# schematic.net
KiCad netlist of a schematic drawn in EAGLE
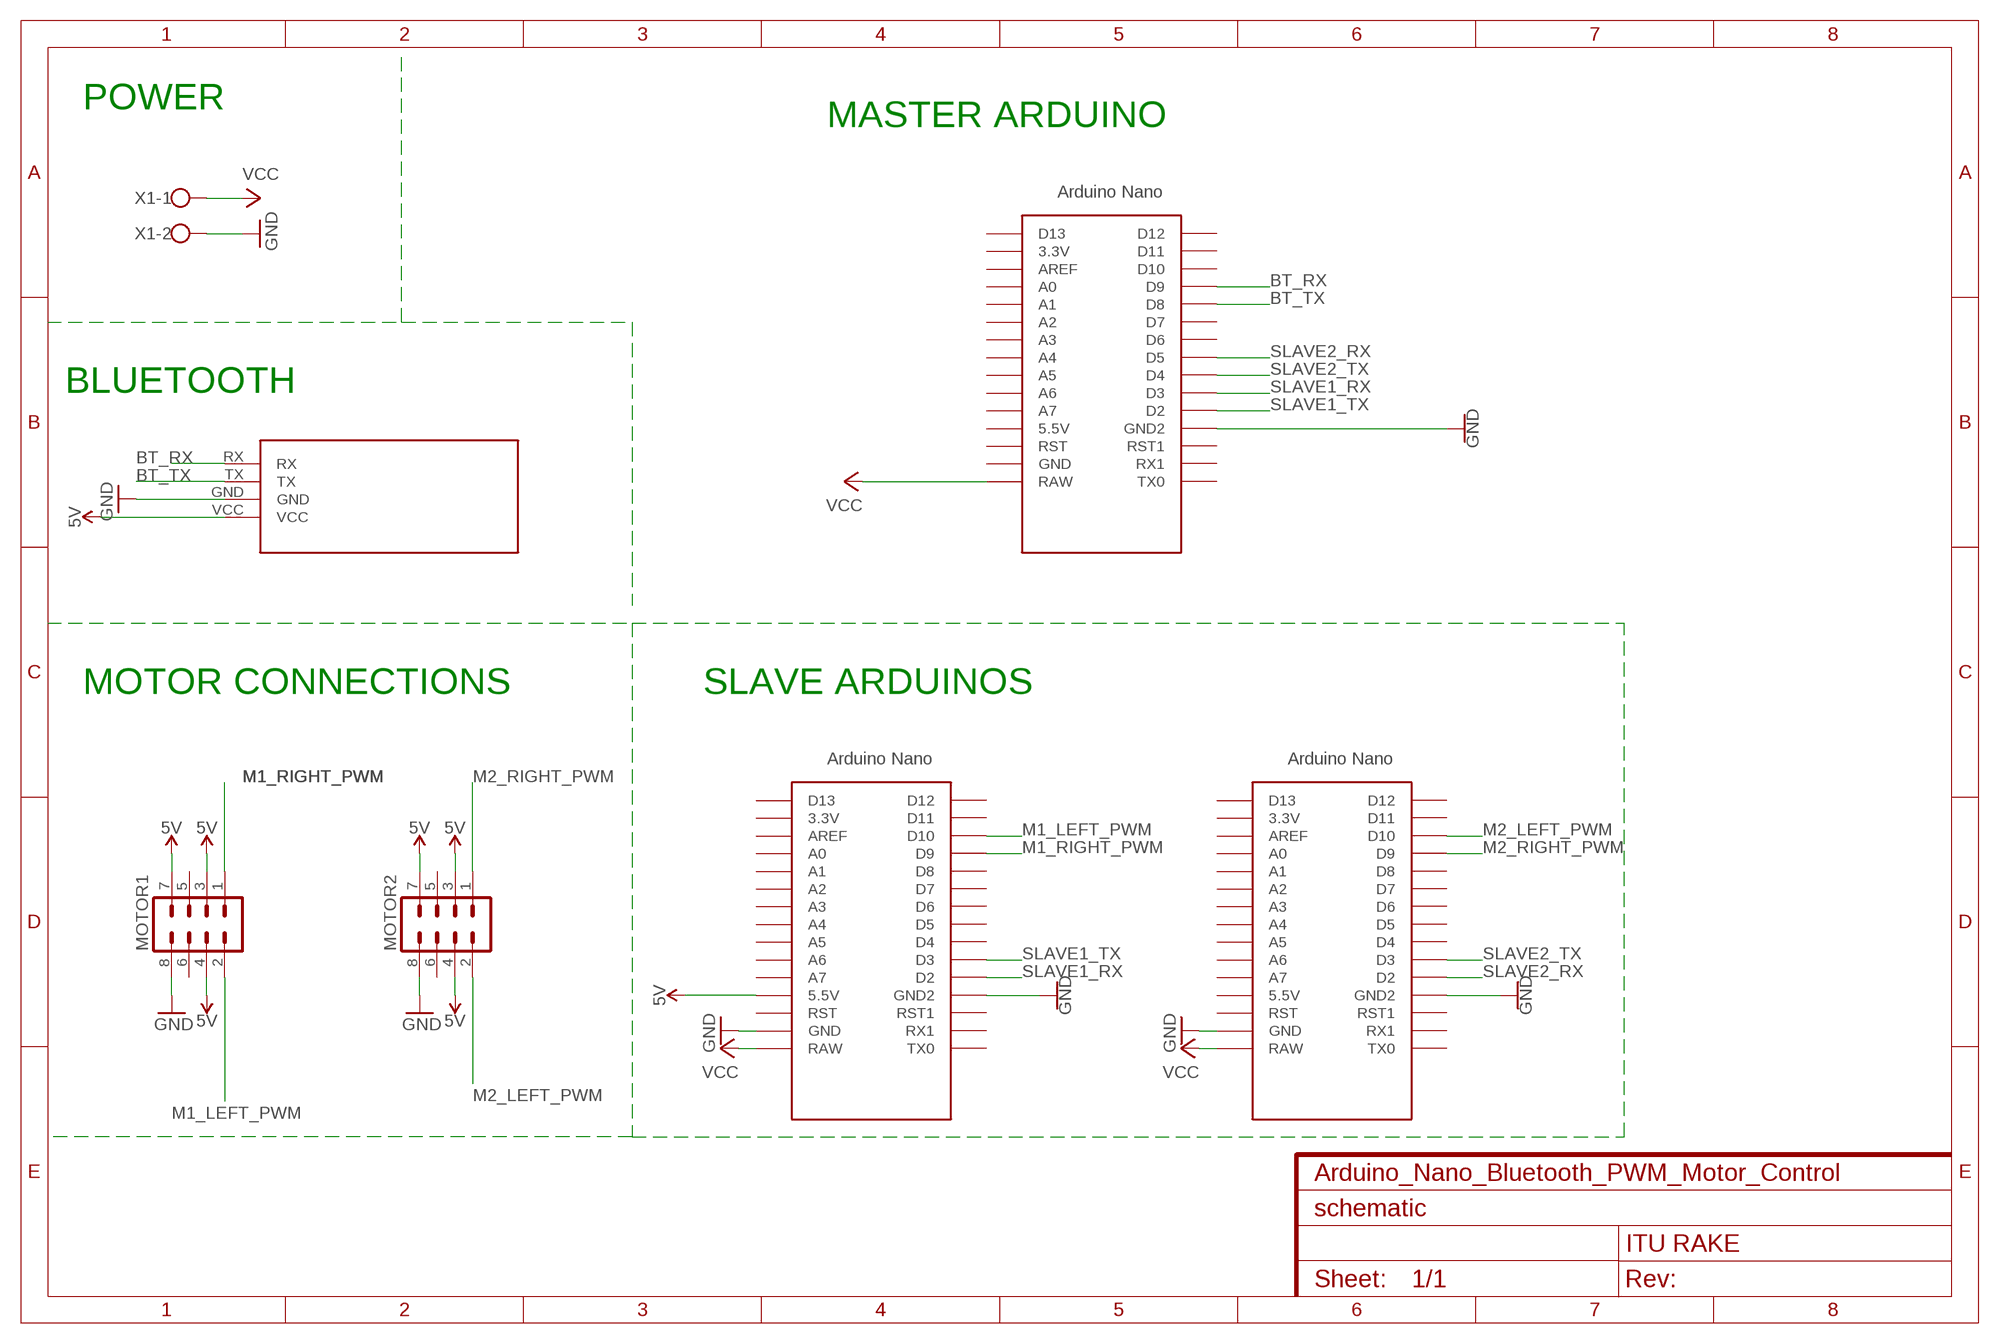
[diagram p0: schematic, sheet 1]

(export (version "E")
  (design (tool "Eeschema 10.0.6"))
  (components
    (comp (ref "BT")
      (value "HC06_BLUETOOTH")
      (footprint "eagle-import:HC06_BT_FOOTPRıNT")
      (libsource (lib "eagle-import") (part "HC06_BLUETOOTH"))
    )
    (comp (ref "MOTOR1")
      (value "MA04-2")
      (footprint "eagle-import:MA04-2")
      (libsource (lib "eagle-import") (part "MA04-2"))
    )
    (comp (ref "MOTOR2")
      (value "MA04-2")
      (footprint "eagle-import:MA04-2")
      (libsource (lib "eagle-import") (part "MA04-2"))
    )
    (comp (ref "U$1")
      (value "NANO")
      (footprint "eagle-import:NANO")
      (libsource (lib "eagle-import") (part "NANO"))
    )
    (comp (ref "U$2")
      (value "NANO")
      (footprint "eagle-import:NANO")
      (libsource (lib "eagle-import") (part "NANO"))
    )
    (comp (ref "U$3")
      (value "NANO")
      (footprint "eagle-import:NANO")
      (libsource (lib "eagle-import") (part "NANO"))
    )
    (comp (ref "X1")
      (value "W237-102")
      (footprint "eagle-import:W237-102")
      (fields (field (name "MPN") "237-102"))
      (libsource (lib "eagle-import") (part "W237-102"))
    )
  )
  (nets
    (net (code "1") (name "/BT_RX") (class "Default")
      (node (ref "BT") (pin "RX") (pinfunction "RX_RX") (pintype "bidirectional"))
      (node (ref "U$1") (pin "D9") (pinfunction "D9_D9") (pintype "bidirectional"))
    )
    (net (code "2") (name "/BT_TX") (class "Default")
      (node (ref "BT") (pin "TX") (pinfunction "TX_TX") (pintype "bidirectional"))
      (node (ref "U$1") (pin "D8") (pinfunction "D8_D8") (pintype "bidirectional"))
    )
    (net (code "3") (name "/M1_LEFT_PWM") (class "Default")
      (node (ref "MOTOR1") (pin "2") (pinfunction "2_2") (pintype "passive"))
      (node (ref "U$2") (pin "D10") (pinfunction "D10_D10") (pintype "bidirectional"))
    )
    (net (code "4") (name "/M1_RIGHT_PWM") (class "Default")
      (node (ref "MOTOR1") (pin "1") (pinfunction "1_1") (pintype "passive"))
      (node (ref "U$2") (pin "D9") (pinfunction "D9_D9") (pintype "bidirectional"))
    )
    (net (code "5") (name "/M2_LEFT_PWM") (class "Default")
      (node (ref "MOTOR2") (pin "2") (pinfunction "2_2") (pintype "passive"))
      (node (ref "U$3") (pin "D10") (pinfunction "D10_D10") (pintype "bidirectional"))
    )
    (net (code "6") (name "/M2_RIGHT_PWM") (class "Default")
      (node (ref "MOTOR2") (pin "1") (pinfunction "1_1") (pintype "passive"))
      (node (ref "U$3") (pin "D9") (pinfunction "D9_D9") (pintype "bidirectional"))
    )
    (net (code "7") (name "/SLAVE1_RX") (class "Default")
      (node (ref "U$1") (pin "D3") (pinfunction "D3_D3") (pintype "bidirectional"))
      (node (ref "U$2") (pin "D2") (pinfunction "D2_D2") (pintype "bidirectional"))
    )
    (net (code "8") (name "/SLAVE1_TX") (class "Default")
      (node (ref "U$1") (pin "D2") (pinfunction "D2_D2") (pintype "bidirectional"))
      (node (ref "U$2") (pin "D3") (pinfunction "D3_D3") (pintype "bidirectional"))
    )
    (net (code "9") (name "/SLAVE2_RX") (class "Default")
      (node (ref "U$1") (pin "D5") (pinfunction "D5_D5") (pintype "bidirectional"))
      (node (ref "U$3") (pin "D2") (pinfunction "D2_D2") (pintype "bidirectional"))
    )
    (net (code "10") (name "/SLAVE2_TX") (class "Default")
      (node (ref "U$1") (pin "D4") (pinfunction "D4_D4") (pintype "bidirectional"))
      (node (ref "U$3") (pin "D3") (pinfunction "D3_D3") (pintype "bidirectional"))
    )
    (net (code "11") (name "5V") (class "Default")
      (node (ref "BT") (pin "VCC") (pinfunction "VCC_VCC") (pintype "bidirectional"))
      (node (ref "MOTOR1") (pin "3") (pinfunction "3_3") (pintype "passive"))
      (node (ref "MOTOR1") (pin "4") (pinfunction "4_4") (pintype "passive"))
      (node (ref "MOTOR1") (pin "7") (pinfunction "7_7") (pintype "passive"))
      (node (ref "MOTOR2") (pin "3") (pinfunction "3_3") (pintype "passive"))
      (node (ref "MOTOR2") (pin "4") (pinfunction "4_4") (pintype "passive"))
      (node (ref "MOTOR2") (pin "7") (pinfunction "7_7") (pintype "passive"))
      (node (ref "U$2") (pin "5V") (pinfunction "5.5V_5V") (pintype "bidirectional"))
    )
    (net (code "12") (name "GND") (class "Default")
      (node (ref "BT") (pin "GND") (pinfunction "GND_GND") (pintype "bidirectional"))
      (node (ref "MOTOR1") (pin "8") (pinfunction "8_8") (pintype "passive"))
      (node (ref "MOTOR2") (pin "8") (pinfunction "8_8") (pintype "passive"))
      (node (ref "U$1") (pin "GND1") (pinfunction "GND2_GND1") (pintype "bidirectional"))
      (node (ref "U$2") (pin "GND") (pinfunction "GND_GND") (pintype "bidirectional"))
      (node (ref "U$2") (pin "GND1") (pinfunction "GND2_GND1") (pintype "bidirectional"))
      (node (ref "U$3") (pin "GND") (pinfunction "GND_GND") (pintype "bidirectional"))
      (node (ref "U$3") (pin "GND1") (pinfunction "GND2_GND1") (pintype "bidirectional"))
      (node (ref "X1") (pin "2") (pinfunction "KL_2") (pintype "passive"))
    )
    (net (code "13") (name "VCC") (class "Default")
      (node (ref "U$1") (pin "RAW") (pinfunction "RAW_RAW") (pintype "bidirectional"))
      (node (ref "U$2") (pin "RAW") (pinfunction "RAW_RAW") (pintype "bidirectional"))
      (node (ref "U$3") (pin "RAW") (pinfunction "RAW_RAW") (pintype "bidirectional"))
      (node (ref "X1") (pin "1") (pinfunction "KL_1") (pintype "passive"))
    )
    (net (code "14") (name "unconnected-(MOTOR1-Pad5)") (class "Default")
      (node (ref "MOTOR1") (pin "5") (pinfunction "5_5") (pintype "passive"))
    )
    (net (code "15") (name "unconnected-(MOTOR1-Pad6)") (class "Default")
      (node (ref "MOTOR1") (pin "6") (pinfunction "6_6") (pintype "passive"))
    )
    (net (code "16") (name "unconnected-(MOTOR2-Pad5)") (class "Default")
      (node (ref "MOTOR2") (pin "5") (pinfunction "5_5") (pintype "passive"))
    )
    (net (code "17") (name "unconnected-(MOTOR2-Pad6)") (class "Default")
      (node (ref "MOTOR2") (pin "6") (pinfunction "6_6") (pintype "passive"))
    )
    (net (code "18") (name "unconnected-(U$1-5.5V-Pad5V)") (class "Default")
      (node (ref "U$1") (pin "5V") (pinfunction "5.5V_5V") (pintype "bidirectional"))
    )
    (net (code "19") (name "unconnected-(U$1-Pad3.3V)") (class "Default")
      (node (ref "U$1") (pin "3.3V") (pinfunction "3.3V_3.3V") (pintype "bidirectional"))
    )
    (net (code "20") (name "unconnected-(U$1-PadA0)") (class "Default")
      (node (ref "U$1") (pin "A0") (pinfunction "A0_A0") (pintype "bidirectional"))
    )
    (net (code "21") (name "unconnected-(U$1-PadA1)") (class "Default")
      (node (ref "U$1") (pin "A1") (pinfunction "A1_A1") (pintype "bidirectional"))
    )
    (net (code "22") (name "unconnected-(U$1-PadA2)") (class "Default")
      (node (ref "U$1") (pin "A2") (pinfunction "A2_A2") (pintype "bidirectional"))
    )
    (net (code "23") (name "unconnected-(U$1-PadA3)") (class "Default")
      (node (ref "U$1") (pin "A3") (pinfunction "A3_A3") (pintype "bidirectional"))
    )
    (net (code "24") (name "unconnected-(U$1-PadA4)") (class "Default")
      (node (ref "U$1") (pin "A4") (pinfunction "A4_A4") (pintype "bidirectional"))
    )
    (net (code "25") (name "unconnected-(U$1-PadA5)") (class "Default")
      (node (ref "U$1") (pin "A5") (pinfunction "A5_A5") (pintype "bidirectional"))
    )
    (net (code "26") (name "unconnected-(U$1-PadA6)") (class "Default")
      (node (ref "U$1") (pin "A6") (pinfunction "A6_A6") (pintype "bidirectional"))
    )
    (net (code "27") (name "unconnected-(U$1-PadA7)") (class "Default")
      (node (ref "U$1") (pin "A7") (pinfunction "A7_A7") (pintype "bidirectional"))
    )
    (net (code "28") (name "unconnected-(U$1-PadAREF)") (class "Default")
      (node (ref "U$1") (pin "AREF") (pinfunction "AREF_AREF") (pintype "bidirectional"))
    )
    (net (code "29") (name "unconnected-(U$1-PadD6)") (class "Default")
      (node (ref "U$1") (pin "D6") (pinfunction "D6_D6") (pintype "bidirectional"))
    )
    (net (code "30") (name "unconnected-(U$1-PadD7)") (class "Default")
      (node (ref "U$1") (pin "D7") (pinfunction "D7_D7") (pintype "bidirectional"))
    )
    (net (code "31") (name "unconnected-(U$1-PadD10)") (class "Default")
      (node (ref "U$1") (pin "D10") (pinfunction "D10_D10") (pintype "bidirectional"))
    )
    (net (code "32") (name "unconnected-(U$1-PadD11)") (class "Default")
      (node (ref "U$1") (pin "D11") (pinfunction "D11_D11") (pintype "bidirectional"))
    )
    (net (code "33") (name "unconnected-(U$1-PadD12)") (class "Default")
      (node (ref "U$1") (pin "D12") (pinfunction "D12_D12") (pintype "bidirectional"))
    )
    (net (code "34") (name "unconnected-(U$1-PadD13)") (class "Default")
      (node (ref "U$1") (pin "D13") (pinfunction "D13_D13") (pintype "bidirectional"))
    )
    (net (code "35") (name "unconnected-(U$1-PadGND)") (class "Default")
      (node (ref "U$1") (pin "GND") (pinfunction "GND_GND") (pintype "bidirectional"))
    )
    (net (code "36") (name "unconnected-(U$1-PadICSP1)") (class "Default")
      (node (ref "U$1") (pin "ICSP1") (pinfunction "ICSP1_ICSP1") (pintype "bidirectional"))
    )
    (net (code "37") (name "unconnected-(U$1-PadICSP2)") (class "Default")
      (node (ref "U$1") (pin "ICSP2") (pinfunction "ICSP2_ICSP2") (pintype "bidirectional"))
    )
    (net (code "38") (name "unconnected-(U$1-PadICSP3)") (class "Default")
      (node (ref "U$1") (pin "ICSP3") (pinfunction "ICSP3_ICSP3") (pintype "bidirectional"))
    )
    (net (code "39") (name "unconnected-(U$1-PadICSP4)") (class "Default")
      (node (ref "U$1") (pin "ICSP4") (pinfunction "ICSP4_ICSP4") (pintype "bidirectional"))
    )
    (net (code "40") (name "unconnected-(U$1-PadICSP5)") (class "Default")
      (node (ref "U$1") (pin "ICSP5") (pinfunction "ICSP5_ICSP5") (pintype "bidirectional"))
    )
    (net (code "41") (name "unconnected-(U$1-PadICSP6)") (class "Default")
      (node (ref "U$1") (pin "ICSP6") (pinfunction "ICSP6_ICSP6") (pintype "bidirectional"))
    )
    (net (code "42") (name "unconnected-(U$1-PadRST)") (class "Default")
      (node (ref "U$1") (pin "RST") (pinfunction "RST_RST") (pintype "bidirectional"))
    )
    (net (code "43") (name "unconnected-(U$1-PadRST1)") (class "Default")
      (node (ref "U$1") (pin "RST1") (pinfunction "RST1_RST1") (pintype "bidirectional"))
    )
    (net (code "44") (name "unconnected-(U$1-PadRX1)") (class "Default")
      (node (ref "U$1") (pin "RX1") (pinfunction "RX1_RX1") (pintype "bidirectional"))
    )
    (net (code "45") (name "unconnected-(U$1-PadTX0)") (class "Default")
      (node (ref "U$1") (pin "TX0") (pinfunction "TX0_TX0") (pintype "bidirectional"))
    )
    (net (code "46") (name "unconnected-(U$2-Pad3.3V)") (class "Default")
      (node (ref "U$2") (pin "3.3V") (pinfunction "3.3V_3.3V") (pintype "bidirectional"))
    )
    (net (code "47") (name "unconnected-(U$2-PadA0)") (class "Default")
      (node (ref "U$2") (pin "A0") (pinfunction "A0_A0") (pintype "bidirectional"))
    )
    (net (code "48") (name "unconnected-(U$2-PadA1)") (class "Default")
      (node (ref "U$2") (pin "A1") (pinfunction "A1_A1") (pintype "bidirectional"))
    )
    (net (code "49") (name "unconnected-(U$2-PadA2)") (class "Default")
      (node (ref "U$2") (pin "A2") (pinfunction "A2_A2") (pintype "bidirectional"))
    )
    (net (code "50") (name "unconnected-(U$2-PadA3)") (class "Default")
      (node (ref "U$2") (pin "A3") (pinfunction "A3_A3") (pintype "bidirectional"))
    )
    (net (code "51") (name "unconnected-(U$2-PadA4)") (class "Default")
      (node (ref "U$2") (pin "A4") (pinfunction "A4_A4") (pintype "bidirectional"))
    )
    (net (code "52") (name "unconnected-(U$2-PadA5)") (class "Default")
      (node (ref "U$2") (pin "A5") (pinfunction "A5_A5") (pintype "bidirectional"))
    )
    (net (code "53") (name "unconnected-(U$2-PadA6)") (class "Default")
      (node (ref "U$2") (pin "A6") (pinfunction "A6_A6") (pintype "bidirectional"))
    )
    (net (code "54") (name "unconnected-(U$2-PadA7)") (class "Default")
      (node (ref "U$2") (pin "A7") (pinfunction "A7_A7") (pintype "bidirectional"))
    )
    (net (code "55") (name "unconnected-(U$2-PadAREF)") (class "Default")
      (node (ref "U$2") (pin "AREF") (pinfunction "AREF_AREF") (pintype "bidirectional"))
    )
    (net (code "56") (name "unconnected-(U$2-PadD4)") (class "Default")
      (node (ref "U$2") (pin "D4") (pinfunction "D4_D4") (pintype "bidirectional"))
    )
    (net (code "57") (name "unconnected-(U$2-PadD5)") (class "Default")
      (node (ref "U$2") (pin "D5") (pinfunction "D5_D5") (pintype "bidirectional"))
    )
    (net (code "58") (name "unconnected-(U$2-PadD6)") (class "Default")
      (node (ref "U$2") (pin "D6") (pinfunction "D6_D6") (pintype "bidirectional"))
    )
    (net (code "59") (name "unconnected-(U$2-PadD7)") (class "Default")
      (node (ref "U$2") (pin "D7") (pinfunction "D7_D7") (pintype "bidirectional"))
    )
    (net (code "60") (name "unconnected-(U$2-PadD8)") (class "Default")
      (node (ref "U$2") (pin "D8") (pinfunction "D8_D8") (pintype "bidirectional"))
    )
    (net (code "61") (name "unconnected-(U$2-PadD11)") (class "Default")
      (node (ref "U$2") (pin "D11") (pinfunction "D11_D11") (pintype "bidirectional"))
    )
    (net (code "62") (name "unconnected-(U$2-PadD12)") (class "Default")
      (node (ref "U$2") (pin "D12") (pinfunction "D12_D12") (pintype "bidirectional"))
    )
    (net (code "63") (name "unconnected-(U$2-PadD13)") (class "Default")
      (node (ref "U$2") (pin "D13") (pinfunction "D13_D13") (pintype "bidirectional"))
    )
    (net (code "64") (name "unconnected-(U$2-PadICSP1)") (class "Default")
      (node (ref "U$2") (pin "ICSP1") (pinfunction "ICSP1_ICSP1") (pintype "bidirectional"))
    )
    (net (code "65") (name "unconnected-(U$2-PadICSP2)") (class "Default")
      (node (ref "U$2") (pin "ICSP2") (pinfunction "ICSP2_ICSP2") (pintype "bidirectional"))
    )
    (net (code "66") (name "unconnected-(U$2-PadICSP3)") (class "Default")
      (node (ref "U$2") (pin "ICSP3") (pinfunction "ICSP3_ICSP3") (pintype "bidirectional"))
    )
    (net (code "67") (name "unconnected-(U$2-PadICSP4)") (class "Default")
      (node (ref "U$2") (pin "ICSP4") (pinfunction "ICSP4_ICSP4") (pintype "bidirectional"))
    )
    (net (code "68") (name "unconnected-(U$2-PadICSP5)") (class "Default")
      (node (ref "U$2") (pin "ICSP5") (pinfunction "ICSP5_ICSP5") (pintype "bidirectional"))
    )
    (net (code "69") (name "unconnected-(U$2-PadICSP6)") (class "Default")
      (node (ref "U$2") (pin "ICSP6") (pinfunction "ICSP6_ICSP6") (pintype "bidirectional"))
    )
    (net (code "70") (name "unconnected-(U$2-PadRST)") (class "Default")
      (node (ref "U$2") (pin "RST") (pinfunction "RST_RST") (pintype "bidirectional"))
    )
    (net (code "71") (name "unconnected-(U$2-PadRST1)") (class "Default")
      (node (ref "U$2") (pin "RST1") (pinfunction "RST1_RST1") (pintype "bidirectional"))
    )
    (net (code "72") (name "unconnected-(U$2-PadRX1)") (class "Default")
      (node (ref "U$2") (pin "RX1") (pinfunction "RX1_RX1") (pintype "bidirectional"))
    )
    (net (code "73") (name "unconnected-(U$2-PadTX0)") (class "Default")
      (node (ref "U$2") (pin "TX0") (pinfunction "TX0_TX0") (pintype "bidirectional"))
    )
    (net (code "74") (name "unconnected-(U$3-5.5V-Pad5V)") (class "Default")
      (node (ref "U$3") (pin "5V") (pinfunction "5.5V_5V") (pintype "bidirectional"))
    )
    (net (code "75") (name "unconnected-(U$3-Pad3.3V)") (class "Default")
      (node (ref "U$3") (pin "3.3V") (pinfunction "3.3V_3.3V") (pintype "bidirectional"))
    )
    (net (code "76") (name "unconnected-(U$3-PadA0)") (class "Default")
      (node (ref "U$3") (pin "A0") (pinfunction "A0_A0") (pintype "bidirectional"))
    )
    (net (code "77") (name "unconnected-(U$3-PadA1)") (class "Default")
      (node (ref "U$3") (pin "A1") (pinfunction "A1_A1") (pintype "bidirectional"))
    )
    (net (code "78") (name "unconnected-(U$3-PadA2)") (class "Default")
      (node (ref "U$3") (pin "A2") (pinfunction "A2_A2") (pintype "bidirectional"))
    )
    (net (code "79") (name "unconnected-(U$3-PadA3)") (class "Default")
      (node (ref "U$3") (pin "A3") (pinfunction "A3_A3") (pintype "bidirectional"))
    )
    (net (code "80") (name "unconnected-(U$3-PadA4)") (class "Default")
      (node (ref "U$3") (pin "A4") (pinfunction "A4_A4") (pintype "bidirectional"))
    )
    (net (code "81") (name "unconnected-(U$3-PadA5)") (class "Default")
      (node (ref "U$3") (pin "A5") (pinfunction "A5_A5") (pintype "bidirectional"))
    )
    (net (code "82") (name "unconnected-(U$3-PadA6)") (class "Default")
      (node (ref "U$3") (pin "A6") (pinfunction "A6_A6") (pintype "bidirectional"))
    )
    (net (code "83") (name "unconnected-(U$3-PadA7)") (class "Default")
      (node (ref "U$3") (pin "A7") (pinfunction "A7_A7") (pintype "bidirectional"))
    )
    (net (code "84") (name "unconnected-(U$3-PadAREF)") (class "Default")
      (node (ref "U$3") (pin "AREF") (pinfunction "AREF_AREF") (pintype "bidirectional"))
    )
    (net (code "85") (name "unconnected-(U$3-PadD4)") (class "Default")
      (node (ref "U$3") (pin "D4") (pinfunction "D4_D4") (pintype "bidirectional"))
    )
    (net (code "86") (name "unconnected-(U$3-PadD5)") (class "Default")
      (node (ref "U$3") (pin "D5") (pinfunction "D5_D5") (pintype "bidirectional"))
    )
    (net (code "87") (name "unconnected-(U$3-PadD6)") (class "Default")
      (node (ref "U$3") (pin "D6") (pinfunction "D6_D6") (pintype "bidirectional"))
    )
    (net (code "88") (name "unconnected-(U$3-PadD7)") (class "Default")
      (node (ref "U$3") (pin "D7") (pinfunction "D7_D7") (pintype "bidirectional"))
    )
    (net (code "89") (name "unconnected-(U$3-PadD8)") (class "Default")
      (node (ref "U$3") (pin "D8") (pinfunction "D8_D8") (pintype "bidirectional"))
    )
    (net (code "90") (name "unconnected-(U$3-PadD11)") (class "Default")
      (node (ref "U$3") (pin "D11") (pinfunction "D11_D11") (pintype "bidirectional"))
    )
    (net (code "91") (name "unconnected-(U$3-PadD12)") (class "Default")
      (node (ref "U$3") (pin "D12") (pinfunction "D12_D12") (pintype "bidirectional"))
    )
    (net (code "92") (name "unconnected-(U$3-PadD13)") (class "Default")
      (node (ref "U$3") (pin "D13") (pinfunction "D13_D13") (pintype "bidirectional"))
    )
    (net (code "93") (name "unconnected-(U$3-PadICSP1)") (class "Default")
      (node (ref "U$3") (pin "ICSP1") (pinfunction "ICSP1_ICSP1") (pintype "bidirectional"))
    )
    (net (code "94") (name "unconnected-(U$3-PadICSP2)") (class "Default")
      (node (ref "U$3") (pin "ICSP2") (pinfunction "ICSP2_ICSP2") (pintype "bidirectional"))
    )
    (net (code "95") (name "unconnected-(U$3-PadICSP3)") (class "Default")
      (node (ref "U$3") (pin "ICSP3") (pinfunction "ICSP3_ICSP3") (pintype "bidirectional"))
    )
    (net (code "96") (name "unconnected-(U$3-PadICSP4)") (class "Default")
      (node (ref "U$3") (pin "ICSP4") (pinfunction "ICSP4_ICSP4") (pintype "bidirectional"))
    )
    (net (code "97") (name "unconnected-(U$3-PadICSP5)") (class "Default")
      (node (ref "U$3") (pin "ICSP5") (pinfunction "ICSP5_ICSP5") (pintype "bidirectional"))
    )
    (net (code "98") (name "unconnected-(U$3-PadICSP6)") (class "Default")
      (node (ref "U$3") (pin "ICSP6") (pinfunction "ICSP6_ICSP6") (pintype "bidirectional"))
    )
    (net (code "99") (name "unconnected-(U$3-PadRST)") (class "Default")
      (node (ref "U$3") (pin "RST") (pinfunction "RST_RST") (pintype "bidirectional"))
    )
    (net (code "100") (name "unconnected-(U$3-PadRST1)") (class "Default")
      (node (ref "U$3") (pin "RST1") (pinfunction "RST1_RST1") (pintype "bidirectional"))
    )
    (net (code "101") (name "unconnected-(U$3-PadRX1)") (class "Default")
      (node (ref "U$3") (pin "RX1") (pinfunction "RX1_RX1") (pintype "bidirectional"))
    )
    (net (code "102") (name "unconnected-(U$3-PadTX0)") (class "Default")
      (node (ref "U$3") (pin "TX0") (pinfunction "TX0_TX0") (pintype "bidirectional"))
    )
  )
)
